# CAMERA.net
KiCad netlist of a schematic drawn in EAGLE
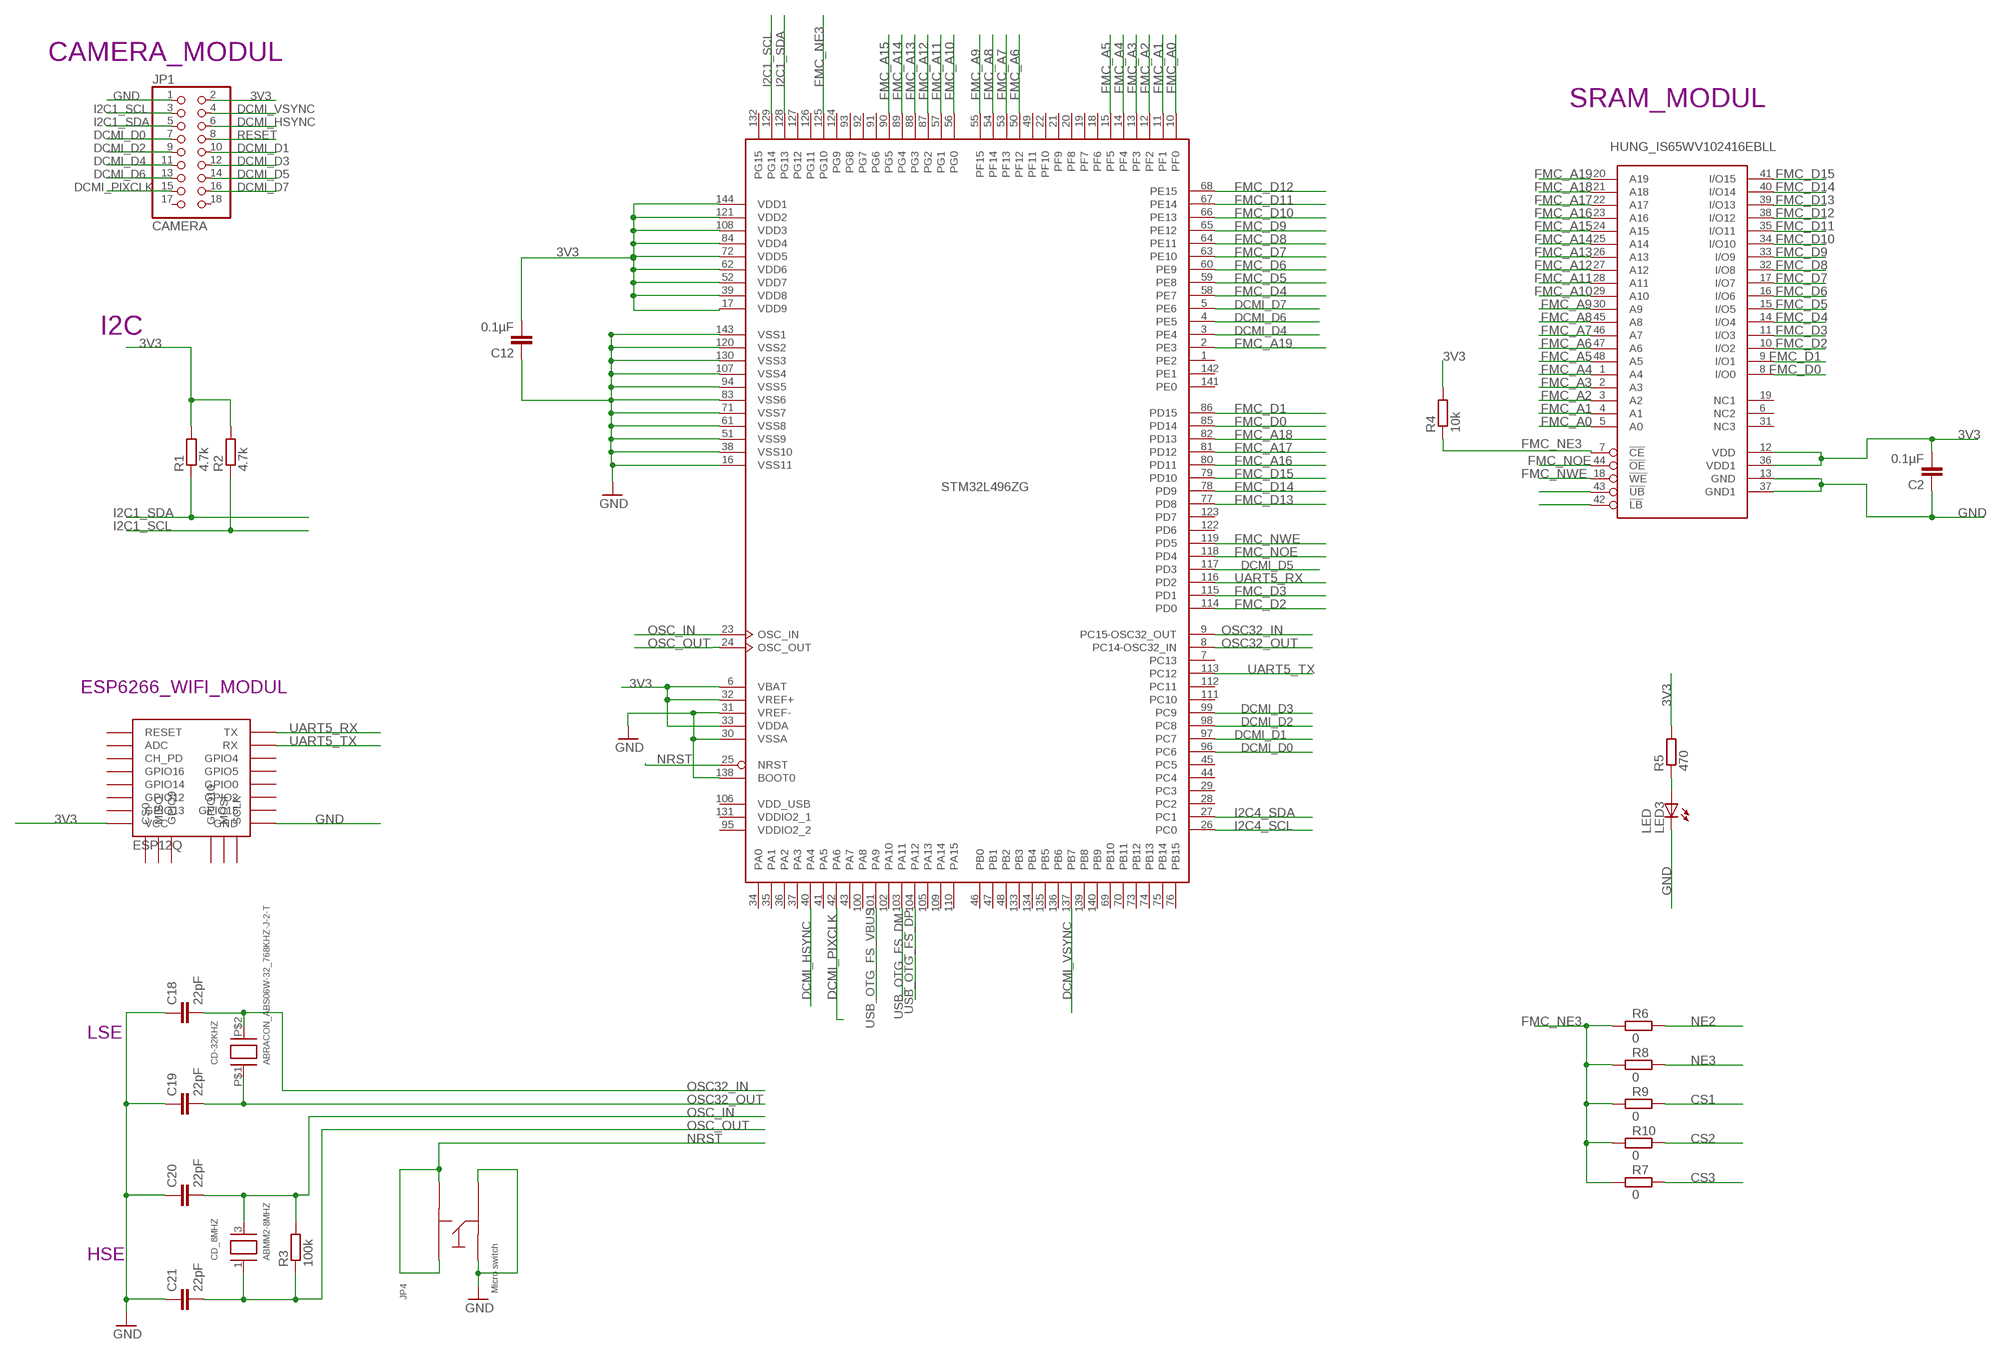
[diagram p0: schematic, sheet 1]
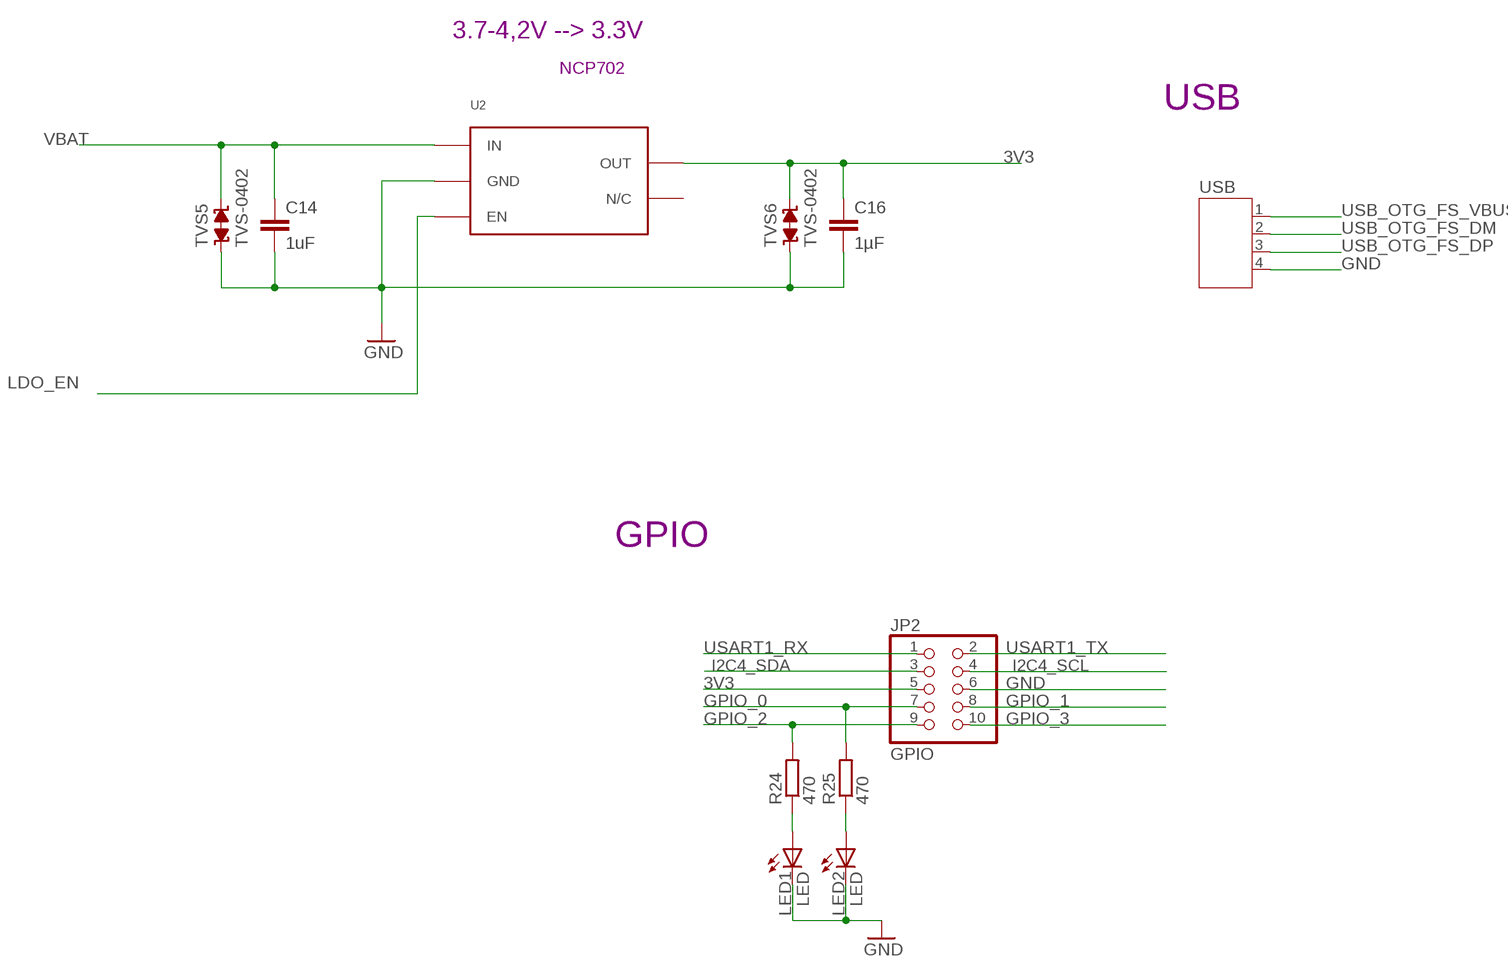
[diagram p1: schematic, sheet 2]

(export (version "E")
  (design (tool "Eeschema 10.0.6"))
  (components
    (comp (ref "C14")
      (value "1uF")
      (footprint "eagle-import:C0402K")
      (libsource (lib "eagle-import") (part "C-EUC0402K"))
    )
    (comp (ref "C16")
      (value "1µF")
      (footprint "eagle-import:C0402K")
      (libsource (lib "eagle-import") (part "C-EUC0402K"))
    )
    (comp (ref "JP2")
      (value "GPIO")
      (footprint "eagle-import:2X05")
      (libsource (lib "eagle-import") (part "PINHD-2X5"))
    )
    (comp (ref "LED1")
      (value "LED")
      (footprint "eagle-import:0603_AK")
      (fields (field (name "MPN") "LB Q39G-L2OO-35-1"))
      (libsource (lib "eagle-import") (part "LED"))
    )
    (comp (ref "LED2")
      (value "LED")
      (footprint "eagle-import:0603_AK")
      (fields (field (name "MPN") "LB Q39G-L2OO-35-1"))
      (libsource (lib "eagle-import") (part "LED"))
    )
    (comp (ref "R24")
      (value "470")
      (footprint "eagle-import:R0402")
      (libsource (lib "eagle-import") (part "R-EU_R0402"))
    )
    (comp (ref "R25")
      (value "470")
      (footprint "eagle-import:R0402")
      (libsource (lib "eagle-import") (part "R-EU_R0402"))
    )
    (comp (ref "TVS5")
      (value "TVS-0402")
      (footprint "eagle-import:TVS0402")
      (fields (field (name "MPN") "GG0402050R3C2P"))
      (libsource (lib "eagle-import") (part "TVS-0402"))
    )
    (comp (ref "TVS6")
      (value "TVS-0402")
      (footprint "eagle-import:TVS0402")
      (fields (field (name "MPN") "GG0402050R3C2P"))
      (libsource (lib "eagle-import") (part "TVS-0402"))
    )
    (comp (ref "U2")
      (value "NCP702")
      (footprint "eagle-import:SOT563")
      (fields (field (name "MOUSER_PART_NUMBER") "863-NCP702SN33T1G"))
      (libsource (lib "eagle-import") (part "NCP702"))
    )
    (comp (ref "USB")
      (value "JST-PH4")
      (footprint "eagle-import:JST-PH4")
      (libsource (lib "eagle-import") (part "JST-PH4"))
    )
    (comp (ref "C2")
      (value "0.1µF")
      (footprint "eagle-import:C0402K")
      (libsource (lib "eagle-import") (part "C-EUC0402K"))
    )
    (comp (ref "C12")
      (value "0.1µF")
      (footprint "eagle-import:C0402K")
      (libsource (lib "eagle-import") (part "C-EUC0402K"))
    )
    (comp (ref "C18")
      (value "22pF")
      (footprint "eagle-import:C0402K")
      (libsource (lib "eagle-import") (part "C-EUC0402K"))
    )
    (comp (ref "C19")
      (value "22pF")
      (footprint "eagle-import:C0402K")
      (libsource (lib "eagle-import") (part "C-EUC0402K"))
    )
    (comp (ref "C20")
      (value "22pF")
      (footprint "eagle-import:C0402K")
      (libsource (lib "eagle-import") (part "C-EUC0402K"))
    )
    (comp (ref "C21")
      (value "22pF")
      (footprint "eagle-import:C0402K")
      (libsource (lib "eagle-import") (part "C-EUC0402K"))
    )
    (comp (ref "CD-32KHZ")
      (value "ABRACON_ABS06W-32_768KHZ-J-2-T")
      (footprint "eagle-import:2MM_X_1_2MM")
      (libsource (lib "eagle-import") (part "ABRACON_ABS06W-32_768KHZ-J-2-T"))
    )
    (comp (ref "CD_8MHZ")
      (value "ABMM2-8MHZ")
      (footprint "eagle-import:CRYSTAL_ABRACON_6MM_3.6MM")
      (fields (field (name "MPN") "ABMM2-8.0000MHZ-E1-T"))
      (libsource (lib "eagle-import") (part "ABMM2-8MHZ"))
    )
    (comp (ref "JP1")
      (value "CAMERA")
      (footprint "eagle-import:2X09")
      (libsource (lib "eagle-import") (part "PINHD-2X9"))
    )
    (comp (ref "JP4")
      (value "MICRO_SWITCH_6MM")
      (footprint "eagle-import:SKQGADE010")
      (fields (field (name "MPN") "SKQGABE010"))
      (libsource (lib "eagle-import") (part "MICRO_SWITCH_6MM"))
    )
    (comp (ref "LED3")
      (value "LED")
      (footprint "eagle-import:0603_AK")
      (fields (field (name "MPN") "LB Q39G-L2OO-35-1"))
      (libsource (lib "eagle-import") (part "LED"))
    )
    (comp (ref "R1")
      (value "4.7k")
      (footprint "eagle-import:C0402K")
      (libsource (lib "eagle-import") (part "R_0402WEB_0402"))
    )
    (comp (ref "R2")
      (value "4.7k")
      (footprint "eagle-import:C0402K")
      (libsource (lib "eagle-import") (part "R_0402WEB_0402"))
    )
    (comp (ref "R3")
      (value "100k")
      (footprint "eagle-import:C0402K")
      (libsource (lib "eagle-import") (part "R_0402WEB_0402"))
    )
    (comp (ref "R4")
      (value "10k")
      (footprint "eagle-import:C0402K")
      (libsource (lib "eagle-import") (part "R_0402WEB_0402"))
    )
    (comp (ref "R5")
      (value "470")
      (footprint "eagle-import:R0402")
      (libsource (lib "eagle-import") (part "R-EU_R0402"))
    )
    (comp (ref "R6")
      (value "0")
      (footprint "eagle-import:R0402")
      (libsource (lib "eagle-import") (part "R-EU_R0402"))
    )
    (comp (ref "R7")
      (value "0")
      (footprint "eagle-import:R0402")
      (libsource (lib "eagle-import") (part "R-EU_R0402"))
    )
    (comp (ref "R8")
      (value "0")
      (footprint "eagle-import:R0402")
      (libsource (lib "eagle-import") (part "R-EU_R0402"))
    )
    (comp (ref "R9")
      (value "0")
      (footprint "eagle-import:R0402")
      (libsource (lib "eagle-import") (part "R-EU_R0402"))
    )
    (comp (ref "R10")
      (value "0")
      (footprint "eagle-import:R0402")
      (libsource (lib "eagle-import") (part "R-EU_R0402"))
    )
    (comp (ref "STM32L496ZG")
      (value "STM32L496ZGT")
      (footprint "eagle-import:LQFP144")
      (libsource (lib "eagle-import") (part "STM32L496ZGT"))
    )
    (comp (ref "U$1")
      (value "HUNG_IS65WV102416EBLL")
      (footprint "eagle-import:TSOP-I-48-12X40MM")
      (libsource (lib "eagle-import") (part "HUNG_IS65WV102416EBLL"))
    )
    (comp (ref "U$2")
      (value "ESP12Q")
      (footprint "eagle-import:ESP12Q")
      (libsource (lib "eagle-import") (part "ESP12Q"))
    )
  )
  (nets
    (net (code "1") (name "3V3") (class "Default")
      (node (ref "C12") (pin "2") (pinfunction "2_2") (pintype "passive"))
      (node (ref "C16") (pin "1") (pinfunction "1_1") (pintype "passive"))
      (node (ref "C2") (pin "2") (pinfunction "2_2") (pintype "passive"))
      (node (ref "JP1") (pin "2") (pinfunction "2_2") (pintype "passive"))
      (node (ref "JP2") (pin "5") (pinfunction "5_5") (pintype "passive"))
      (node (ref "R1") (pin "2") (pinfunction "2_2") (pintype "passive"))
      (node (ref "R2") (pin "2") (pinfunction "2_2") (pintype "passive"))
      (node (ref "R4") (pin "2") (pinfunction "2_2") (pintype "passive"))
      (node (ref "R5") (pin "2") (pinfunction "2_2") (pintype "passive"))
      (node (ref "STM32L496ZG") (pin "108") (pinfunction "VDD3_108") (pintype "bidirectional"))
      (node (ref "STM32L496ZG") (pin "121") (pinfunction "VDD2_121") (pintype "bidirectional"))
      (node (ref "STM32L496ZG") (pin "144") (pinfunction "VDD1_144") (pintype "bidirectional"))
      (node (ref "STM32L496ZG") (pin "17") (pinfunction "VDD9_17") (pintype "bidirectional"))
      (node (ref "STM32L496ZG") (pin "32") (pinfunction "VREF+_32") (pintype "power_in"))
      (node (ref "STM32L496ZG") (pin "33") (pinfunction "VDDA_33") (pintype "power_in"))
      (node (ref "STM32L496ZG") (pin "39") (pinfunction "VDD8_39") (pintype "bidirectional"))
      (node (ref "STM32L496ZG") (pin "52") (pinfunction "VDD7_52") (pintype "bidirectional"))
      (node (ref "STM32L496ZG") (pin "6") (pinfunction "VBAT_6") (pintype "power_in"))
      (node (ref "STM32L496ZG") (pin "62") (pinfunction "VDD6_62") (pintype "bidirectional"))
      (node (ref "STM32L496ZG") (pin "72") (pinfunction "VDD5_72") (pintype "bidirectional"))
      (node (ref "STM32L496ZG") (pin "84") (pinfunction "VDD4_84") (pintype "bidirectional"))
      (node (ref "TVS6") (pin "2") (pinfunction "2_2") (pintype "passive"))
      (node (ref "U$1") (pin "12") (pinfunction "VDD_12") (pintype "bidirectional"))
      (node (ref "U$1") (pin "36") (pinfunction "VDD1_36") (pintype "bidirectional"))
      (node (ref "U$2") (pin "VCC") (pinfunction "VCC_VCC") (pintype "bidirectional"))
      (node (ref "U2") (pin "P$5") (pinfunction "OUT_P$5") (pintype "bidirectional"))
    )
    (net (code "2") (name "CS1") (class "Default")
      (node (ref "R9") (pin "2") (pinfunction "2_2") (pintype "passive"))
    )
    (net (code "3") (name "CS2") (class "Default")
      (node (ref "R10") (pin "2") (pinfunction "2_2") (pintype "passive"))
    )
    (net (code "4") (name "CS3") (class "Default")
      (node (ref "R7") (pin "2") (pinfunction "2_2") (pintype "passive"))
    )
    (net (code "5") (name "DCMI_D0") (class "Default")
      (node (ref "JP1") (pin "7") (pinfunction "7_7") (pintype "passive"))
      (node (ref "STM32L496ZG") (pin "96") (pinfunction "PC6_96") (pintype "bidirectional"))
    )
    (net (code "6") (name "DCMI_D1") (class "Default")
      (node (ref "JP1") (pin "10") (pinfunction "10_10") (pintype "passive"))
      (node (ref "STM32L496ZG") (pin "97") (pinfunction "PC7_97") (pintype "bidirectional"))
    )
    (net (code "7") (name "DCMI_D2") (class "Default")
      (node (ref "JP1") (pin "9") (pinfunction "9_9") (pintype "passive"))
      (node (ref "STM32L496ZG") (pin "98") (pinfunction "PC8_98") (pintype "bidirectional"))
    )
    (net (code "8") (name "DCMI_D3") (class "Default")
      (node (ref "JP1") (pin "12") (pinfunction "12_12") (pintype "passive"))
      (node (ref "STM32L496ZG") (pin "99") (pinfunction "PC9_99") (pintype "bidirectional"))
    )
    (net (code "9") (name "DCMI_D4") (class "Default")
      (node (ref "JP1") (pin "11") (pinfunction "11_11") (pintype "passive"))
      (node (ref "STM32L496ZG") (pin "3") (pinfunction "PE4_3") (pintype "bidirectional"))
    )
    (net (code "10") (name "DCMI_D5") (class "Default")
      (node (ref "JP1") (pin "14") (pinfunction "14_14") (pintype "passive"))
      (node (ref "STM32L496ZG") (pin "117") (pinfunction "PD3_117") (pintype "bidirectional"))
    )
    (net (code "11") (name "DCMI_D6") (class "Default")
      (node (ref "JP1") (pin "13") (pinfunction "13_13") (pintype "passive"))
      (node (ref "STM32L496ZG") (pin "4") (pinfunction "PE5_4") (pintype "bidirectional"))
    )
    (net (code "12") (name "DCMI_D7") (class "Default")
      (node (ref "JP1") (pin "16") (pinfunction "16_16") (pintype "passive"))
      (node (ref "STM32L496ZG") (pin "5") (pinfunction "PE6_5") (pintype "bidirectional"))
    )
    (net (code "13") (name "DCMI_HSYNC") (class "Default")
      (node (ref "JP1") (pin "6") (pinfunction "6_6") (pintype "passive"))
      (node (ref "STM32L496ZG") (pin "40") (pinfunction "PA4_40") (pintype "bidirectional"))
    )
    (net (code "14") (name "DCMI_PIXCLK") (class "Default")
      (node (ref "JP1") (pin "15") (pinfunction "15_15") (pintype "passive"))
      (node (ref "STM32L496ZG") (pin "42") (pinfunction "PA6_42") (pintype "bidirectional"))
    )
    (net (code "15") (name "DCMI_VSYNC") (class "Default")
      (node (ref "JP1") (pin "4") (pinfunction "4_4") (pintype "passive"))
      (node (ref "STM32L496ZG") (pin "137") (pinfunction "PB7_137") (pintype "bidirectional"))
    )
    (net (code "16") (name "FMC_A0") (class "Default")
      (node (ref "STM32L496ZG") (pin "10") (pinfunction "PF0_10") (pintype "bidirectional"))
      (node (ref "U$1") (pin "5") (pinfunction "A0_5") (pintype "input"))
    )
    (net (code "17") (name "FMC_A1") (class "Default")
      (node (ref "STM32L496ZG") (pin "11") (pinfunction "PF1_11") (pintype "bidirectional"))
      (node (ref "U$1") (pin "4") (pinfunction "A1_4") (pintype "input"))
    )
    (net (code "18") (name "FMC_A2") (class "Default")
      (node (ref "STM32L496ZG") (pin "12") (pinfunction "PF2_12") (pintype "bidirectional"))
      (node (ref "U$1") (pin "3") (pinfunction "A2_3") (pintype "input"))
    )
    (net (code "19") (name "FMC_A3") (class "Default")
      (node (ref "STM32L496ZG") (pin "13") (pinfunction "PF3_13") (pintype "bidirectional"))
      (node (ref "U$1") (pin "2") (pinfunction "A3_2") (pintype "input"))
    )
    (net (code "20") (name "FMC_A4") (class "Default")
      (node (ref "STM32L496ZG") (pin "14") (pinfunction "PF4_14") (pintype "bidirectional"))
      (node (ref "U$1") (pin "1") (pinfunction "A4_1") (pintype "input"))
    )
    (net (code "21") (name "FMC_A5") (class "Default")
      (node (ref "STM32L496ZG") (pin "15") (pinfunction "PF5_15") (pintype "bidirectional"))
      (node (ref "U$1") (pin "48") (pinfunction "A5_48") (pintype "input"))
    )
    (net (code "22") (name "FMC_A6") (class "Default")
      (node (ref "STM32L496ZG") (pin "50") (pinfunction "PF12_50") (pintype "bidirectional"))
      (node (ref "U$1") (pin "47") (pinfunction "A6_47") (pintype "input"))
    )
    (net (code "23") (name "FMC_A7") (class "Default")
      (node (ref "STM32L496ZG") (pin "53") (pinfunction "PF13_53") (pintype "bidirectional"))
      (node (ref "U$1") (pin "46") (pinfunction "A7_46") (pintype "input"))
    )
    (net (code "24") (name "FMC_A8") (class "Default")
      (node (ref "STM32L496ZG") (pin "54") (pinfunction "PF14_54") (pintype "bidirectional"))
      (node (ref "U$1") (pin "45") (pinfunction "A8_45") (pintype "input"))
    )
    (net (code "25") (name "FMC_A9") (class "Default")
      (node (ref "STM32L496ZG") (pin "55") (pinfunction "PF15_55") (pintype "bidirectional"))
      (node (ref "U$1") (pin "30") (pinfunction "A9_30") (pintype "input"))
    )
    (net (code "26") (name "FMC_A10") (class "Default")
      (node (ref "STM32L496ZG") (pin "56") (pinfunction "PG0_56") (pintype "bidirectional"))
      (node (ref "U$1") (pin "29") (pinfunction "A10_29") (pintype "input"))
    )
    (net (code "27") (name "FMC_A11") (class "Default")
      (node (ref "STM32L496ZG") (pin "57") (pinfunction "PG1_57") (pintype "bidirectional"))
      (node (ref "U$1") (pin "28") (pinfunction "A11_28") (pintype "input"))
    )
    (net (code "28") (name "FMC_A12") (class "Default")
      (node (ref "STM32L496ZG") (pin "87") (pinfunction "PG2_87") (pintype "bidirectional"))
      (node (ref "U$1") (pin "27") (pinfunction "A12_27") (pintype "input"))
    )
    (net (code "29") (name "FMC_A13") (class "Default")
      (node (ref "STM32L496ZG") (pin "88") (pinfunction "PG3_88") (pintype "bidirectional"))
      (node (ref "U$1") (pin "26") (pinfunction "A13_26") (pintype "input"))
    )
    (net (code "30") (name "FMC_A14") (class "Default")
      (node (ref "STM32L496ZG") (pin "89") (pinfunction "PG4_89") (pintype "bidirectional"))
      (node (ref "U$1") (pin "25") (pinfunction "A14_25") (pintype "input"))
    )
    (net (code "31") (name "FMC_A15") (class "Default")
      (node (ref "STM32L496ZG") (pin "90") (pinfunction "PG5_90") (pintype "bidirectional"))
      (node (ref "U$1") (pin "24") (pinfunction "A15_24") (pintype "input"))
    )
    (net (code "32") (name "FMC_A16") (class "Default")
      (node (ref "STM32L496ZG") (pin "80") (pinfunction "PD11_80") (pintype "bidirectional"))
      (node (ref "U$1") (pin "23") (pinfunction "A16_23") (pintype "input"))
    )
    (net (code "33") (name "FMC_A17") (class "Default")
      (node (ref "STM32L496ZG") (pin "81") (pinfunction "PD12_81") (pintype "bidirectional"))
      (node (ref "U$1") (pin "22") (pinfunction "A17_22") (pintype "input"))
    )
    (net (code "34") (name "FMC_A18") (class "Default")
      (node (ref "STM32L496ZG") (pin "82") (pinfunction "PD13_82") (pintype "bidirectional"))
      (node (ref "U$1") (pin "21") (pinfunction "A18_21") (pintype "input"))
    )
    (net (code "35") (name "FMC_A19") (class "Default")
      (node (ref "STM32L496ZG") (pin "2") (pinfunction "PE3_2") (pintype "bidirectional"))
      (node (ref "U$1") (pin "20") (pinfunction "A19_20") (pintype "input"))
    )
    (net (code "36") (name "FMC_D0") (class "Default")
      (node (ref "STM32L496ZG") (pin "85") (pinfunction "PD14_85") (pintype "bidirectional"))
      (node (ref "U$1") (pin "8") (pinfunction "I/O0_8") (pintype "tri_state"))
    )
    (net (code "37") (name "FMC_D1") (class "Default")
      (node (ref "STM32L496ZG") (pin "86") (pinfunction "PD15_86") (pintype "bidirectional"))
      (node (ref "U$1") (pin "9") (pinfunction "I/O1_9") (pintype "tri_state"))
    )
    (net (code "38") (name "FMC_D2") (class "Default")
      (node (ref "STM32L496ZG") (pin "114") (pinfunction "PD0_114") (pintype "bidirectional"))
      (node (ref "U$1") (pin "10") (pinfunction "I/O2_10") (pintype "tri_state"))
    )
    (net (code "39") (name "FMC_D3") (class "Default")
      (node (ref "STM32L496ZG") (pin "115") (pinfunction "PD1_115") (pintype "bidirectional"))
      (node (ref "U$1") (pin "11") (pinfunction "I/O3_11") (pintype "tri_state"))
    )
    (net (code "40") (name "FMC_D4") (class "Default")
      (node (ref "STM32L496ZG") (pin "58") (pinfunction "PE7_58") (pintype "bidirectional"))
      (node (ref "U$1") (pin "14") (pinfunction "I/O4_14") (pintype "tri_state"))
    )
    (net (code "41") (name "FMC_D5") (class "Default")
      (node (ref "STM32L496ZG") (pin "59") (pinfunction "PE8_59") (pintype "bidirectional"))
      (node (ref "U$1") (pin "15") (pinfunction "I/O5_15") (pintype "tri_state"))
    )
    (net (code "42") (name "FMC_D6") (class "Default")
      (node (ref "STM32L496ZG") (pin "60") (pinfunction "PE9_60") (pintype "bidirectional"))
      (node (ref "U$1") (pin "16") (pinfunction "I/O6_16") (pintype "tri_state"))
    )
    (net (code "43") (name "FMC_D7") (class "Default")
      (node (ref "STM32L496ZG") (pin "63") (pinfunction "PE10_63") (pintype "bidirectional"))
      (node (ref "U$1") (pin "17") (pinfunction "I/O7_17") (pintype "tri_state"))
    )
    (net (code "44") (name "FMC_D8") (class "Default")
      (node (ref "STM32L496ZG") (pin "64") (pinfunction "PE11_64") (pintype "bidirectional"))
      (node (ref "U$1") (pin "32") (pinfunction "I/O8_32") (pintype "tri_state"))
    )
    (net (code "45") (name "FMC_D9") (class "Default")
      (node (ref "STM32L496ZG") (pin "65") (pinfunction "PE12_65") (pintype "bidirectional"))
      (node (ref "U$1") (pin "33") (pinfunction "I/O9_33") (pintype "tri_state"))
    )
    (net (code "46") (name "FMC_D10") (class "Default")
      (node (ref "STM32L496ZG") (pin "66") (pinfunction "PE13_66") (pintype "bidirectional"))
      (node (ref "U$1") (pin "34") (pinfunction "I/O10_34") (pintype "tri_state"))
    )
    (net (code "47") (name "FMC_D11") (class "Default")
      (node (ref "STM32L496ZG") (pin "67") (pinfunction "PE14_67") (pintype "bidirectional"))
      (node (ref "U$1") (pin "35") (pinfunction "I/O11_35") (pintype "tri_state"))
    )
    (net (code "48") (name "FMC_D12") (class "Default")
      (node (ref "STM32L496ZG") (pin "68") (pinfunction "PE15_68") (pintype "bidirectional"))
      (node (ref "U$1") (pin "38") (pinfunction "I/O12_38") (pintype "tri_state"))
    )
    (net (code "49") (name "FMC_D13") (class "Default")
      (node (ref "STM32L496ZG") (pin "77") (pinfunction "PD8_77") (pintype "bidirectional"))
      (node (ref "U$1") (pin "39") (pinfunction "I/O13_39") (pintype "tri_state"))
    )
    (net (code "50") (name "FMC_D14") (class "Default")
      (node (ref "STM32L496ZG") (pin "78") (pinfunction "PD9_78") (pintype "bidirectional"))
      (node (ref "U$1") (pin "40") (pinfunction "I/O14_40") (pintype "tri_state"))
    )
    (net (code "51") (name "FMC_D15") (class "Default")
      (node (ref "STM32L496ZG") (pin "79") (pinfunction "PD10_79") (pintype "bidirectional"))
      (node (ref "U$1") (pin "41") (pinfunction "I/O15_41") (pintype "tri_state"))
    )
    (net (code "52") (name "FMC_NE3") (class "Default")
      (node (ref "R10") (pin "1") (pinfunction "1_1") (pintype "passive"))
      (node (ref "R4") (pin "1") (pinfunction "1_1") (pintype "passive"))
      (node (ref "R6") (pin "1") (pinfunction "1_1") (pintype "passive"))
      (node (ref "R7") (pin "1") (pinfunction "1_1") (pintype "passive"))
      (node (ref "R8") (pin "1") (pinfunction "1_1") (pintype "passive"))
      (node (ref "R9") (pin "1") (pinfunction "1_1") (pintype "passive"))
      (node (ref "STM32L496ZG") (pin "125") (pinfunction "PG10_125") (pintype "bidirectional"))
      (node (ref "U$1") (pin "7") (pinfunction "~{CE}_7") (pintype "input"))
    )
    (net (code "53") (name "FMC_NOE") (class "Default")
      (node (ref "STM32L496ZG") (pin "118") (pinfunction "PD4_118") (pintype "bidirectional"))
      (node (ref "U$1") (pin "44") (pinfunction "~{OE}_44") (pintype "input"))
    )
    (net (code "54") (name "FMC_NWE") (class "Default")
      (node (ref "STM32L496ZG") (pin "119") (pinfunction "PD5_119") (pintype "bidirectional"))
      (node (ref "U$1") (pin "18") (pinfunction "~{WE}_18") (pintype "input"))
    )
    (net (code "55") (name "GND") (class "Default")
      (node (ref "C12") (pin "1") (pinfunction "1_1") (pintype "passive"))
      (node (ref "C14") (pin "2") (pinfunction "2_2") (pintype "passive"))
      (node (ref "C16") (pin "2") (pinfunction "2_2") (pintype "passive"))
      (node (ref "C18") (pin "1") (pinfunction "1_1") (pintype "passive"))
      (node (ref "C19") (pin "1") (pinfunction "1_1") (pintype "passive"))
      (node (ref "C2") (pin "1") (pinfunction "1_1") (pintype "passive"))
      (node (ref "C20") (pin "1") (pinfunction "1_1") (pintype "passive"))
      (node (ref "C21") (pin "1") (pinfunction "1_1") (pintype "passive"))
      (node (ref "JP1") (pin "1") (pinfunction "1_1") (pintype "passive"))
      (node (ref "JP2") (pin "6") (pinfunction "6_6") (pintype "passive"))
      (node (ref "JP4") (pin "P$3") (pinfunction "P$3_P$3") (pintype "bidirectional"))
      (node (ref "JP4") (pin "P$4") (pinfunction "P$4_P$4") (pintype "bidirectional"))
      (node (ref "LED1") (pin "K") (pinfunction "C_K") (pintype "passive"))
      (node (ref "LED2") (pin "K") (pinfunction "C_K") (pintype "passive"))
      (node (ref "LED3") (pin "K") (pinfunction "C_K") (pintype "passive"))
      (node (ref "STM32L496ZG") (pin "107") (pinfunction "VSS4_107") (pintype "bidirectional"))
      (node (ref "STM32L496ZG") (pin "120") (pinfunction "VSS2_120") (pintype "bidirectional"))
      (node (ref "STM32L496ZG") (pin "130") (pinfunction "VSS3_130") (pintype "bidirectional"))
      (node (ref "STM32L496ZG") (pin "138") (pinfunction "BOOT0_138") (pintype "input"))
      (node (ref "STM32L496ZG") (pin "143") (pinfunction "VSS1_143") (pintype "bidirectional"))
      (node (ref "STM32L496ZG") (pin "16") (pinfunction "VSS11_16") (pintype "bidirectional"))
      (node (ref "STM32L496ZG") (pin "30") (pinfunction "VSSA_30") (pintype "power_in"))
      (node (ref "STM32L496ZG") (pin "31") (pinfunction "VREF-_31") (pintype "power_in"))
      (node (ref "STM32L496ZG") (pin "38") (pinfunction "VSS10_38") (pintype "bidirectional"))
      (node (ref "STM32L496ZG") (pin "51") (pinfunction "VSS9_51") (pintype "bidirectional"))
      (node (ref "STM32L496ZG") (pin "61") (pinfunction "VSS8_61") (pintype "bidirectional"))
      (node (ref "STM32L496ZG") (pin "71") (pinfunction "VSS7_71") (pintype "bidirectional"))
      (node (ref "STM32L496ZG") (pin "83") (pinfunction "VSS6_83") (pintype "bidirectional"))
      (node (ref "STM32L496ZG") (pin "94") (pinfunction "VSS5_94") (pintype "bidirectional"))
      (node (ref "TVS5") (pin "1") (pinfunction "1_1") (pintype "passive"))
      (node (ref "TVS6") (pin "1") (pinfunction "1_1") (pintype "passive"))
      (node (ref "U$1") (pin "13") (pinfunction "GND_13") (pintype "bidirectional"))
      (node (ref "U$1") (pin "37") (pinfunction "GND1_37") (pintype "bidirectional"))
      (node (ref "U$2") (pin "GND") (pinfunction "GND_GND") (pintype "bidirectional"))
      (node (ref "U2") (pin "P$2") (pinfunction "GND_P$2") (pintype "bidirectional"))
      (node (ref "USB") (pin "4") (pinfunction "4_4") (pintype "passive"))
    )
    (net (code "56") (name "GPIO_0") (class "Default")
      (node (ref "JP2") (pin "7") (pinfunction "7_7") (pintype "passive"))
      (node (ref "R25") (pin "2") (pinfunction "2_2") (pintype "passive"))
    )
    (net (code "57") (name "GPIO_1") (class "Default")
      (node (ref "JP2") (pin "8") (pinfunction "8_8") (pintype "passive"))
    )
    (net (code "58") (name "GPIO_2") (class "Default")
      (node (ref "JP2") (pin "9") (pinfunction "9_9") (pintype "passive"))
      (node (ref "R24") (pin "2") (pinfunction "2_2") (pintype "passive"))
    )
    (net (code "59") (name "GPIO_3") (class "Default")
      (node (ref "JP2") (pin "10") (pinfunction "10_10") (pintype "passive"))
    )
    (net (code "60") (name "I2C1_SCL") (class "Default")
      (node (ref "JP1") (pin "3") (pinfunction "3_3") (pintype "passive"))
      (node (ref "R2") (pin "1") (pinfunction "1_1") (pintype "passive"))
      (node (ref "STM32L496ZG") (pin "129") (pinfunction "PG14_129") (pintype "bidirectional"))
    )
    (net (code "61") (name "I2C1_SDA") (class "Default")
      (node (ref "JP1") (pin "5") (pinfunction "5_5") (pintype "passive"))
      (node (ref "R1") (pin "1") (pinfunction "1_1") (pintype "passive"))
      (node (ref "STM32L496ZG") (pin "128") (pinfunction "PG13_128") (pintype "bidirectional"))
    )
    (net (code "62") (name "I2C4_SCL") (class "Default")
      (node (ref "JP2") (pin "4") (pinfunction "4_4") (pintype "passive"))
      (node (ref "STM32L496ZG") (pin "26") (pinfunction "PC0_26") (pintype "bidirectional"))
    )
    (net (code "63") (name "I2C4_SDA") (class "Default")
      (node (ref "JP2") (pin "3") (pinfunction "3_3") (pintype "passive"))
      (node (ref "STM32L496ZG") (pin "27") (pinfunction "PC1_27") (pintype "bidirectional"))
    )
    (net (code "64") (name "LDO_EN") (class "Default")
      (node (ref "U2") (pin "P$3") (pinfunction "EN_P$3") (pintype "bidirectional"))
    )
    (net (code "65") (name "NE2") (class "Default")
      (node (ref "R6") (pin "2") (pinfunction "2_2") (pintype "passive"))
    )
    (net (code "66") (name "NE3") (class "Default")
      (node (ref "R8") (pin "2") (pinfunction "2_2") (pintype "passive"))
    )
    (net (code "67") (name "NRST") (class "Default")
      (node (ref "JP4") (pin "P$1") (pinfunction "P$1_P$1") (pintype "bidirectional"))
      (node (ref "JP4") (pin "P$2") (pinfunction "P$2_P$2") (pintype "bidirectional"))
      (node (ref "STM32L496ZG") (pin "25") (pinfunction "NRST_25") (pintype "bidirectional"))
    )
    (net (code "68") (name "Net-(LED1-PadA)") (class "Default")
      (node (ref "LED1") (pin "A") (pinfunction "A_A") (pintype "passive"))
      (node (ref "R24") (pin "1") (pinfunction "1_1") (pintype "passive"))
    )
    (net (code "69") (name "Net-(LED2-PadA)") (class "Default")
      (node (ref "LED2") (pin "A") (pinfunction "A_A") (pintype "passive"))
      (node (ref "R25") (pin "1") (pinfunction "1_1") (pintype "passive"))
    )
    (net (code "70") (name "Net-(LED3-PadA)") (class "Default")
      (node (ref "LED3") (pin "A") (pinfunction "A_A") (pintype "passive"))
      (node (ref "R5") (pin "1") (pinfunction "1_1") (pintype "passive"))
    )
    (net (code "71") (name "OSC32_IN") (class "Default")
      (node (ref "C18") (pin "2") (pinfunction "2_2") (pintype "passive"))
      (node (ref "CD-32KHZ") (pin "P$2") (pinfunction "C1_P$2") (pintype "bidirectional"))
      (node (ref "STM32L496ZG") (pin "9") (pinfunction "PC15-OSC32_OUT_9") (pintype "bidirectional"))
    )
    (net (code "72") (name "OSC32_OUT") (class "Default")
      (node (ref "C19") (pin "2") (pinfunction "2_2") (pintype "passive"))
      (node (ref "CD-32KHZ") (pin "P$1") (pinfunction "C0_P$1") (pintype "bidirectional"))
      (node (ref "STM32L496ZG") (pin "8") (pinfunction "PC14-OSC32_IN_8") (pintype "bidirectional"))
    )
    (net (code "73") (name "OSC_IN") (class "Default")
      (node (ref "C20") (pin "2") (pinfunction "2_2") (pintype "passive"))
      (node (ref "CD_8MHZ") (pin "3") (pinfunction "C1_3") (pintype "bidirectional"))
      (node (ref "R3") (pin "2") (pinfunction "2_2") (pintype "passive"))
      (node (ref "STM32L496ZG") (pin "23") (pinfunction "OSC_IN_23") (pintype "bidirectional"))
    )
    (net (code "74") (name "OSC_OUT") (class "Default")
      (node (ref "C21") (pin "2") (pinfunction "2_2") (pintype "passive"))
      (node (ref "CD_8MHZ") (pin "1") (pinfunction "C0_1") (pintype "bidirectional"))
      (node (ref "R3") (pin "1") (pinfunction "1_1") (pintype "passive"))
      (node (ref "STM32L496ZG") (pin "24") (pinfunction "OSC_OUT_24") (pintype "bidirectional"))
    )
    (net (code "75") (name "RESET") (class "Default")
      (node (ref "JP1") (pin "8") (pinfunction "8_8") (pintype "passive"))
    )
    (net (code "76") (name "UART5_RX") (class "Default")
      (node (ref "STM32L496ZG") (pin "116") (pinfunction "PD2_116") (pintype "bidirectional"))
      (node (ref "U$2") (pin "TX") (pinfunction "TX_TX") (pintype "bidirectional"))
    )
    (net (code "77") (name "UART5_TX") (class "Default")
      (node (ref "STM32L496ZG") (pin "113") (pinfunction "PC12_113") (pintype "bidirectional"))
      (node (ref "U$2") (pin "RX") (pinfunction "RX_RX") (pintype "bidirectional"))
    )
    (net (code "78") (name "USART1_RX") (class "Default")
      (node (ref "JP2") (pin "1") (pinfunction "1_1") (pintype "passive"))
    )
    (net (code "79") (name "USART1_TX") (class "Default")
      (node (ref "JP2") (pin "2") (pinfunction "2_2") (pintype "passive"))
    )
    (net (code "80") (name "USB_OTG_FS_DM") (class "Default")
      (node (ref "STM32L496ZG") (pin "103") (pinfunction "PA11_103") (pintype "bidirectional"))
      (node (ref "USB") (pin "2") (pinfunction "2_2") (pintype "passive"))
    )
    (net (code "81") (name "USB_OTG_FS_DP") (class "Default")
      (node (ref "STM32L496ZG") (pin "104") (pinfunction "PA12_104") (pintype "bidirectional"))
      (node (ref "USB") (pin "3") (pinfunction "3_3") (pintype "passive"))
    )
    (net (code "82") (name "USB_OTG_FS_VBUS") (class "Default")
      (node (ref "STM32L496ZG") (pin "101") (pinfunction "PA9_101") (pintype "bidirectional"))
      (node (ref "USB") (pin "1") (pinfunction "1_1") (pintype "passive"))
    )
    (net (code "83") (name "VBAT") (class "Default")
      (node (ref "C14") (pin "1") (pinfunction "1_1") (pintype "passive"))
      (node (ref "TVS5") (pin "2") (pinfunction "2_2") (pintype "passive"))
      (node (ref "U2") (pin "P$1") (pinfunction "IN_P$1") (pintype "bidirectional"))
    )
    (net (code "84") (name "unconnected-(JP1-Pad17)") (class "Default")
      (node (ref "JP1") (pin "17") (pinfunction "17_17") (pintype "passive"))
    )
    (net (code "85") (name "unconnected-(JP1-Pad18)") (class "Default")
      (node (ref "JP1") (pin "18") (pinfunction "18_18") (pintype "passive"))
    )
    (net (code "86") (name "unconnected-(STM32L496ZG-PA0-Pad34)") (class "Default")
      (node (ref "STM32L496ZG") (pin "34") (pinfunction "PA0_34") (pintype "bidirectional"))
    )
    (net (code "87") (name "unconnected-(STM32L496ZG-PA1-Pad35)") (class "Default")
      (node (ref "STM32L496ZG") (pin "35") (pinfunction "PA1_35") (pintype "bidirectional"))
    )
    (net (code "88") (name "unconnected-(STM32L496ZG-PA2-Pad36)") (class "Default")
      (node (ref "STM32L496ZG") (pin "36") (pinfunction "PA2_36") (pintype "bidirectional"))
    )
    (net (code "89") (name "unconnected-(STM32L496ZG-PA3-Pad37)") (class "Default")
      (node (ref "STM32L496ZG") (pin "37") (pinfunction "PA3_37") (pintype "bidirectional"))
    )
    (net (code "90") (name "unconnected-(STM32L496ZG-PA5-Pad41)") (class "Default")
      (node (ref "STM32L496ZG") (pin "41") (pinfunction "PA5_41") (pintype "bidirectional"))
    )
    (net (code "91") (name "unconnected-(STM32L496ZG-PA7-Pad43)") (class "Default")
      (node (ref "STM32L496ZG") (pin "43") (pinfunction "PA7_43") (pintype "bidirectional"))
    )
    (net (code "92") (name "unconnected-(STM32L496ZG-PA8-Pad100)") (class "Default")
      (node (ref "STM32L496ZG") (pin "100") (pinfunction "PA8_100") (pintype "bidirectional"))
    )
    (net (code "93") (name "unconnected-(STM32L496ZG-PA10-Pad102)") (class "Default")
      (node (ref "STM32L496ZG") (pin "102") (pinfunction "PA10_102") (pintype "bidirectional"))
    )
    (net (code "94") (name "unconnected-(STM32L496ZG-PA13-Pad105)") (class "Default")
      (node (ref "STM32L496ZG") (pin "105") (pinfunction "PA13_105") (pintype "bidirectional"))
    )
    (net (code "95") (name "unconnected-(STM32L496ZG-PA14-Pad109)") (class "Default")
      (node (ref "STM32L496ZG") (pin "109") (pinfunction "PA14_109") (pintype "bidirectional"))
    )
    (net (code "96") (name "unconnected-(STM32L496ZG-PA15-Pad110)") (class "Default")
      (node (ref "STM32L496ZG") (pin "110") (pinfunction "PA15_110") (pintype "bidirectional"))
    )
    (net (code "97") (name "unconnected-(STM32L496ZG-PB0-Pad46)") (class "Default")
      (node (ref "STM32L496ZG") (pin "46") (pinfunction "PB0_46") (pintype "bidirectional"))
    )
    (net (code "98") (name "unconnected-(STM32L496ZG-PB1-Pad47)") (class "Default")
      (node (ref "STM32L496ZG") (pin "47") (pinfunction "PB1_47") (pintype "bidirectional"))
    )
    (net (code "99") (name "unconnected-(STM32L496ZG-PB2-Pad48)") (class "Default")
      (node (ref "STM32L496ZG") (pin "48") (pinfunction "PB2_48") (pintype "bidirectional"))
    )
    (net (code "100") (name "unconnected-(STM32L496ZG-PB3-Pad133)") (class "Default")
      (node (ref "STM32L496ZG") (pin "133") (pinfunction "PB3_133") (pintype "bidirectional"))
    )
    (net (code "101") (name "unconnected-(STM32L496ZG-PB4-Pad134)") (class "Default")
      (node (ref "STM32L496ZG") (pin "134") (pinfunction "PB4_134") (pintype "bidirectional"))
    )
    (net (code "102") (name "unconnected-(STM32L496ZG-PB5-Pad135)") (class "Default")
      (node (ref "STM32L496ZG") (pin "135") (pinfunction "PB5_135") (pintype "bidirectional"))
    )
    (net (code "103") (name "unconnected-(STM32L496ZG-PB6-Pad136)") (class "Default")
      (node (ref "STM32L496ZG") (pin "136") (pinfunction "PB6_136") (pintype "bidirectional"))
    )
    (net (code "104") (name "unconnected-(STM32L496ZG-PB8-Pad139)") (class "Default")
      (node (ref "STM32L496ZG") (pin "139") (pinfunction "PB8_139") (pintype "bidirectional"))
    )
    (net (code "105") (name "unconnected-(STM32L496ZG-PB9-Pad140)") (class "Default")
      (node (ref "STM32L496ZG") (pin "140") (pinfunction "PB9_140") (pintype "bidirectional"))
    )
    (net (code "106") (name "unconnected-(STM32L496ZG-PB10-Pad69)") (class "Default")
      (node (ref "STM32L496ZG") (pin "69") (pinfunction "PB10_69") (pintype "bidirectional"))
    )
    (net (code "107") (name "unconnected-(STM32L496ZG-PB11-Pad70)") (class "Default")
      (node (ref "STM32L496ZG") (pin "70") (pinfunction "PB11_70") (pintype "bidirectional"))
    )
    (net (code "108") (name "unconnected-(STM32L496ZG-PB12-Pad73)") (class "Default")
      (node (ref "STM32L496ZG") (pin "73") (pinfunction "PB12_73") (pintype "bidirectional"))
    )
    (net (code "109") (name "unconnected-(STM32L496ZG-PB13-Pad74)") (class "Default")
      (node (ref "STM32L496ZG") (pin "74") (pinfunction "PB13_74") (pintype "bidirectional"))
    )
    (net (code "110") (name "unconnected-(STM32L496ZG-PB14-Pad75)") (class "Default")
      (node (ref "STM32L496ZG") (pin "75") (pinfunction "PB14_75") (pintype "bidirectional"))
    )
    (net (code "111") (name "unconnected-(STM32L496ZG-PB15-Pad76)") (class "Default")
      (node (ref "STM32L496ZG") (pin "76") (pinfunction "PB15_76") (pintype "bidirectional"))
    )
    (net (code "112") (name "unconnected-(STM32L496ZG-PC2-Pad28)") (class "Default")
      (node (ref "STM32L496ZG") (pin "28") (pinfunction "PC2_28") (pintype "bidirectional"))
    )
    (net (code "113") (name "unconnected-(STM32L496ZG-PC3-Pad29)") (class "Default")
      (node (ref "STM32L496ZG") (pin "29") (pinfunction "PC3_29") (pintype "bidirectional"))
    )
    (net (code "114") (name "unconnected-(STM32L496ZG-PC4-Pad44)") (class "Default")
      (node (ref "STM32L496ZG") (pin "44") (pinfunction "PC4_44") (pintype "bidirectional"))
    )
    (net (code "115") (name "unconnected-(STM32L496ZG-PC5-Pad45)") (class "Default")
      (node (ref "STM32L496ZG") (pin "45") (pinfunction "PC5_45") (pintype "bidirectional"))
    )
    (net (code "116") (name "unconnected-(STM32L496ZG-PC10-Pad111)") (class "Default")
      (node (ref "STM32L496ZG") (pin "111") (pinfunction "PC10_111") (pintype "bidirectional"))
    )
    (net (code "117") (name "unconnected-(STM32L496ZG-PC11-Pad112)") (class "Default")
      (node (ref "STM32L496ZG") (pin "112") (pinfunction "PC11_112") (pintype "bidirectional"))
    )
    (net (code "118") (name "unconnected-(STM32L496ZG-PC13-Pad7)") (class "Default")
      (node (ref "STM32L496ZG") (pin "7") (pinfunction "PC13_7") (pintype "bidirectional"))
    )
    (net (code "119") (name "unconnected-(STM32L496ZG-PD6-Pad122)") (class "Default")
      (node (ref "STM32L496ZG") (pin "122") (pinfunction "PD6_122") (pintype "bidirectional"))
    )
    (net (code "120") (name "unconnected-(STM32L496ZG-PD7-Pad123)") (class "Default")
      (node (ref "STM32L496ZG") (pin "123") (pinfunction "PD7_123") (pintype "bidirectional"))
    )
    (net (code "121") (name "unconnected-(STM32L496ZG-PE0-Pad141)") (class "Default")
      (node (ref "STM32L496ZG") (pin "141") (pinfunction "PE0_141") (pintype "bidirectional"))
    )
    (net (code "122") (name "unconnected-(STM32L496ZG-PE1-Pad142)") (class "Default")
      (node (ref "STM32L496ZG") (pin "142") (pinfunction "PE1_142") (pintype "bidirectional"))
    )
    (net (code "123") (name "unconnected-(STM32L496ZG-PE2-Pad1)") (class "Default")
      (node (ref "STM32L496ZG") (pin "1") (pinfunction "PE2_1") (pintype "bidirectional"))
    )
    (net (code "124") (name "unconnected-(STM32L496ZG-PF6-Pad18)") (class "Default")
      (node (ref "STM32L496ZG") (pin "18") (pinfunction "PF6_18") (pintype "bidirectional"))
    )
    (net (code "125") (name "unconnected-(STM32L496ZG-PF7-Pad19)") (class "Default")
      (node (ref "STM32L496ZG") (pin "19") (pinfunction "PF7_19") (pintype "bidirectional"))
    )
    (net (code "126") (name "unconnected-(STM32L496ZG-PF8-Pad20)") (class "Default")
      (node (ref "STM32L496ZG") (pin "20") (pinfunction "PF8_20") (pintype "bidirectional"))
    )
    (net (code "127") (name "unconnected-(STM32L496ZG-PF9-Pad21)") (class "Default")
      (node (ref "STM32L496ZG") (pin "21") (pinfunction "PF9_21") (pintype "bidirectional"))
    )
    (net (code "128") (name "unconnected-(STM32L496ZG-PF10-Pad22)") (class "Default")
      (node (ref "STM32L496ZG") (pin "22") (pinfunction "PF10_22") (pintype "bidirectional"))
    )
    (net (code "129") (name "unconnected-(STM32L496ZG-PF11-Pad49)") (class "Default")
      (node (ref "STM32L496ZG") (pin "49") (pinfunction "PF11_49") (pintype "bidirectional"))
    )
    (net (code "130") (name "unconnected-(STM32L496ZG-PG6-Pad91)") (class "Default")
      (node (ref "STM32L496ZG") (pin "91") (pinfunction "PG6_91") (pintype "bidirectional"))
    )
    (net (code "131") (name "unconnected-(STM32L496ZG-PG7-Pad92)") (class "Default")
      (node (ref "STM32L496ZG") (pin "92") (pinfunction "PG7_92") (pintype "bidirectional"))
    )
    (net (code "132") (name "unconnected-(STM32L496ZG-PG8-Pad93)") (class "Default")
      (node (ref "STM32L496ZG") (pin "93") (pinfunction "PG8_93") (pintype "bidirectional"))
    )
    (net (code "133") (name "unconnected-(STM32L496ZG-PG9-Pad124)") (class "Default")
      (node (ref "STM32L496ZG") (pin "124") (pinfunction "PG9_124") (pintype "bidirectional"))
    )
    (net (code "134") (name "unconnected-(STM32L496ZG-PG11-Pad126)") (class "Default")
      (node (ref "STM32L496ZG") (pin "126") (pinfunction "PG11_126") (pintype "bidirectional"))
    )
    (net (code "135") (name "unconnected-(STM32L496ZG-PG12-Pad127)") (class "Default")
      (node (ref "STM32L496ZG") (pin "127") (pinfunction "PG12_127") (pintype "bidirectional"))
    )
    (net (code "136") (name "unconnected-(STM32L496ZG-PG15-Pad132)") (class "Default")
      (node (ref "STM32L496ZG") (pin "132") (pinfunction "PG15_132") (pintype "bidirectional"))
    )
    (net (code "137") (name "unconnected-(STM32L496ZG-VDDIO2_1-Pad131)") (class "Default")
      (node (ref "STM32L496ZG") (pin "131") (pinfunction "VDDIO2_1_131") (pintype "bidirectional"))
    )
    (net (code "138") (name "unconnected-(STM32L496ZG-VDDIO2_2-Pad95)") (class "Default")
      (node (ref "STM32L496ZG") (pin "95") (pinfunction "VDDIO2_2_95") (pintype "bidirectional"))
    )
    (net (code "139") (name "unconnected-(STM32L496ZG-VDD_USB-Pad106)") (class "Default")
      (node (ref "STM32L496ZG") (pin "106") (pinfunction "VDD_USB_106") (pintype "bidirectional"))
    )
    (net (code "140") (name "unconnected-(U$1-NC1-Pad19)") (class "Default")
      (node (ref "U$1") (pin "19") (pinfunction "NC1_19") (pintype "bidirectional"))
    )
    (net (code "141") (name "unconnected-(U$1-NC2-Pad6)") (class "Default")
      (node (ref "U$1") (pin "6") (pinfunction "NC2_6") (pintype "bidirectional"))
    )
    (net (code "142") (name "unconnected-(U$1-NC3-Pad31)") (class "Default")
      (node (ref "U$1") (pin "31") (pinfunction "NC3_31") (pintype "bidirectional"))
    )
    (net (code "143") (name "unconnected-(U$1-~{LB}-Pad42)") (class "Default")
      (node (ref "U$1") (pin "42") (pinfunction "~{LB}_42") (pintype "input"))
    )
    (net (code "144") (name "unconnected-(U$1-~{UB}-Pad43)") (class "Default")
      (node (ref "U$1") (pin "43") (pinfunction "~{UB}_43") (pintype "input"))
    )
    (net (code "145") (name "unconnected-(U$2-PadADC)") (class "Default")
      (node (ref "U$2") (pin "ADC") (pinfunction "ADC_ADC") (pintype "bidirectional"))
    )
    (net (code "146") (name "unconnected-(U$2-PadCH_PD)") (class "Default")
      (node (ref "U$2") (pin "CH_PD") (pinfunction "CH_PD_CH_PD") (pintype "bidirectional"))
    )
    (net (code "147") (name "unconnected-(U$2-PadCS0)") (class "Default")
      (node (ref "U$2") (pin "CS0") (pinfunction "CS0_CS0") (pintype "bidirectional"))
    )
    (net (code "148") (name "unconnected-(U$2-PadGPIO0)") (class "Default")
      (node (ref "U$2") (pin "GPIO0") (pinfunction "GPIO0_GPIO0") (pintype "bidirectional"))
    )
    (net (code "149") (name "unconnected-(U$2-PadGPIO2)") (class "Default")
      (node (ref "U$2") (pin "GPIO2") (pinfunction "GPIO2_GPIO2") (pintype "bidirectional"))
    )
    (net (code "150") (name "unconnected-(U$2-PadGPIO4)") (class "Default")
      (node (ref "U$2") (pin "GPIO4") (pinfunction "GPIO4_GPIO4") (pintype "bidirectional"))
    )
    (net (code "151") (name "unconnected-(U$2-PadGPIO5)") (class "Default")
      (node (ref "U$2") (pin "GPIO5") (pinfunction "GPIO5_GPIO5") (pintype "bidirectional"))
    )
    (net (code "152") (name "unconnected-(U$2-PadGPIO9)") (class "Default")
      (node (ref "U$2") (pin "GPIO9") (pinfunction "GPIO9_GPIO9") (pintype "bidirectional"))
    )
    (net (code "153") (name "unconnected-(U$2-PadGPIO10)") (class "Default")
      (node (ref "U$2") (pin "GPIO10") (pinfunction "GPIO10_GPIO10") (pintype "bidirectional"))
    )
    (net (code "154") (name "unconnected-(U$2-PadGPIO12)") (class "Default")
      (node (ref "U$2") (pin "GPIO12") (pinfunction "GPIO12_GPIO12") (pintype "bidirectional"))
    )
    (net (code "155") (name "unconnected-(U$2-PadGPIO13)") (class "Default")
      (node (ref "U$2") (pin "GPIO13") (pinfunction "GPIO13_GPIO13") (pintype "bidirectional"))
    )
    (net (code "156") (name "unconnected-(U$2-PadGPIO14)") (class "Default")
      (node (ref "U$2") (pin "GPIO14") (pinfunction "GPIO14_GPIO14") (pintype "bidirectional"))
    )
    (net (code "157") (name "unconnected-(U$2-PadGPIO15)") (class "Default")
      (node (ref "U$2") (pin "GPIO15") (pinfunction "GPIO15_GPIO15") (pintype "bidirectional"))
    )
    (net (code "158") (name "unconnected-(U$2-PadGPIO16)") (class "Default")
      (node (ref "U$2") (pin "GPIO16") (pinfunction "GPIO16_GPIO16") (pintype "bidirectional"))
    )
    (net (code "159") (name "unconnected-(U$2-PadMISO)") (class "Default")
      (node (ref "U$2") (pin "MISO") (pinfunction "MISO_MISO") (pintype "bidirectional"))
    )
    (net (code "160") (name "unconnected-(U$2-PadMOSI)") (class "Default")
      (node (ref "U$2") (pin "MOSI") (pinfunction "MOSI_MOSI") (pintype "bidirectional"))
    )
    (net (code "161") (name "unconnected-(U$2-PadRESET)") (class "Default")
      (node (ref "U$2") (pin "RESET") (pinfunction "RESET_RESET") (pintype "bidirectional"))
    )
    (net (code "162") (name "unconnected-(U$2-PadSCLK)") (class "Default")
      (node (ref "U$2") (pin "SCLK") (pinfunction "SCLK_SCLK") (pintype "bidirectional"))
    )
    (net (code "163") (name "unconnected-(U2-N{slash}C-PadP$4)") (class "Default")
      (node (ref "U2") (pin "P$4") (pinfunction "N/C_P$4") (pintype "no_connect"))
    )
  )
)
